# qfp100.net
KiCad netlist of a schematic drawn in EAGLE
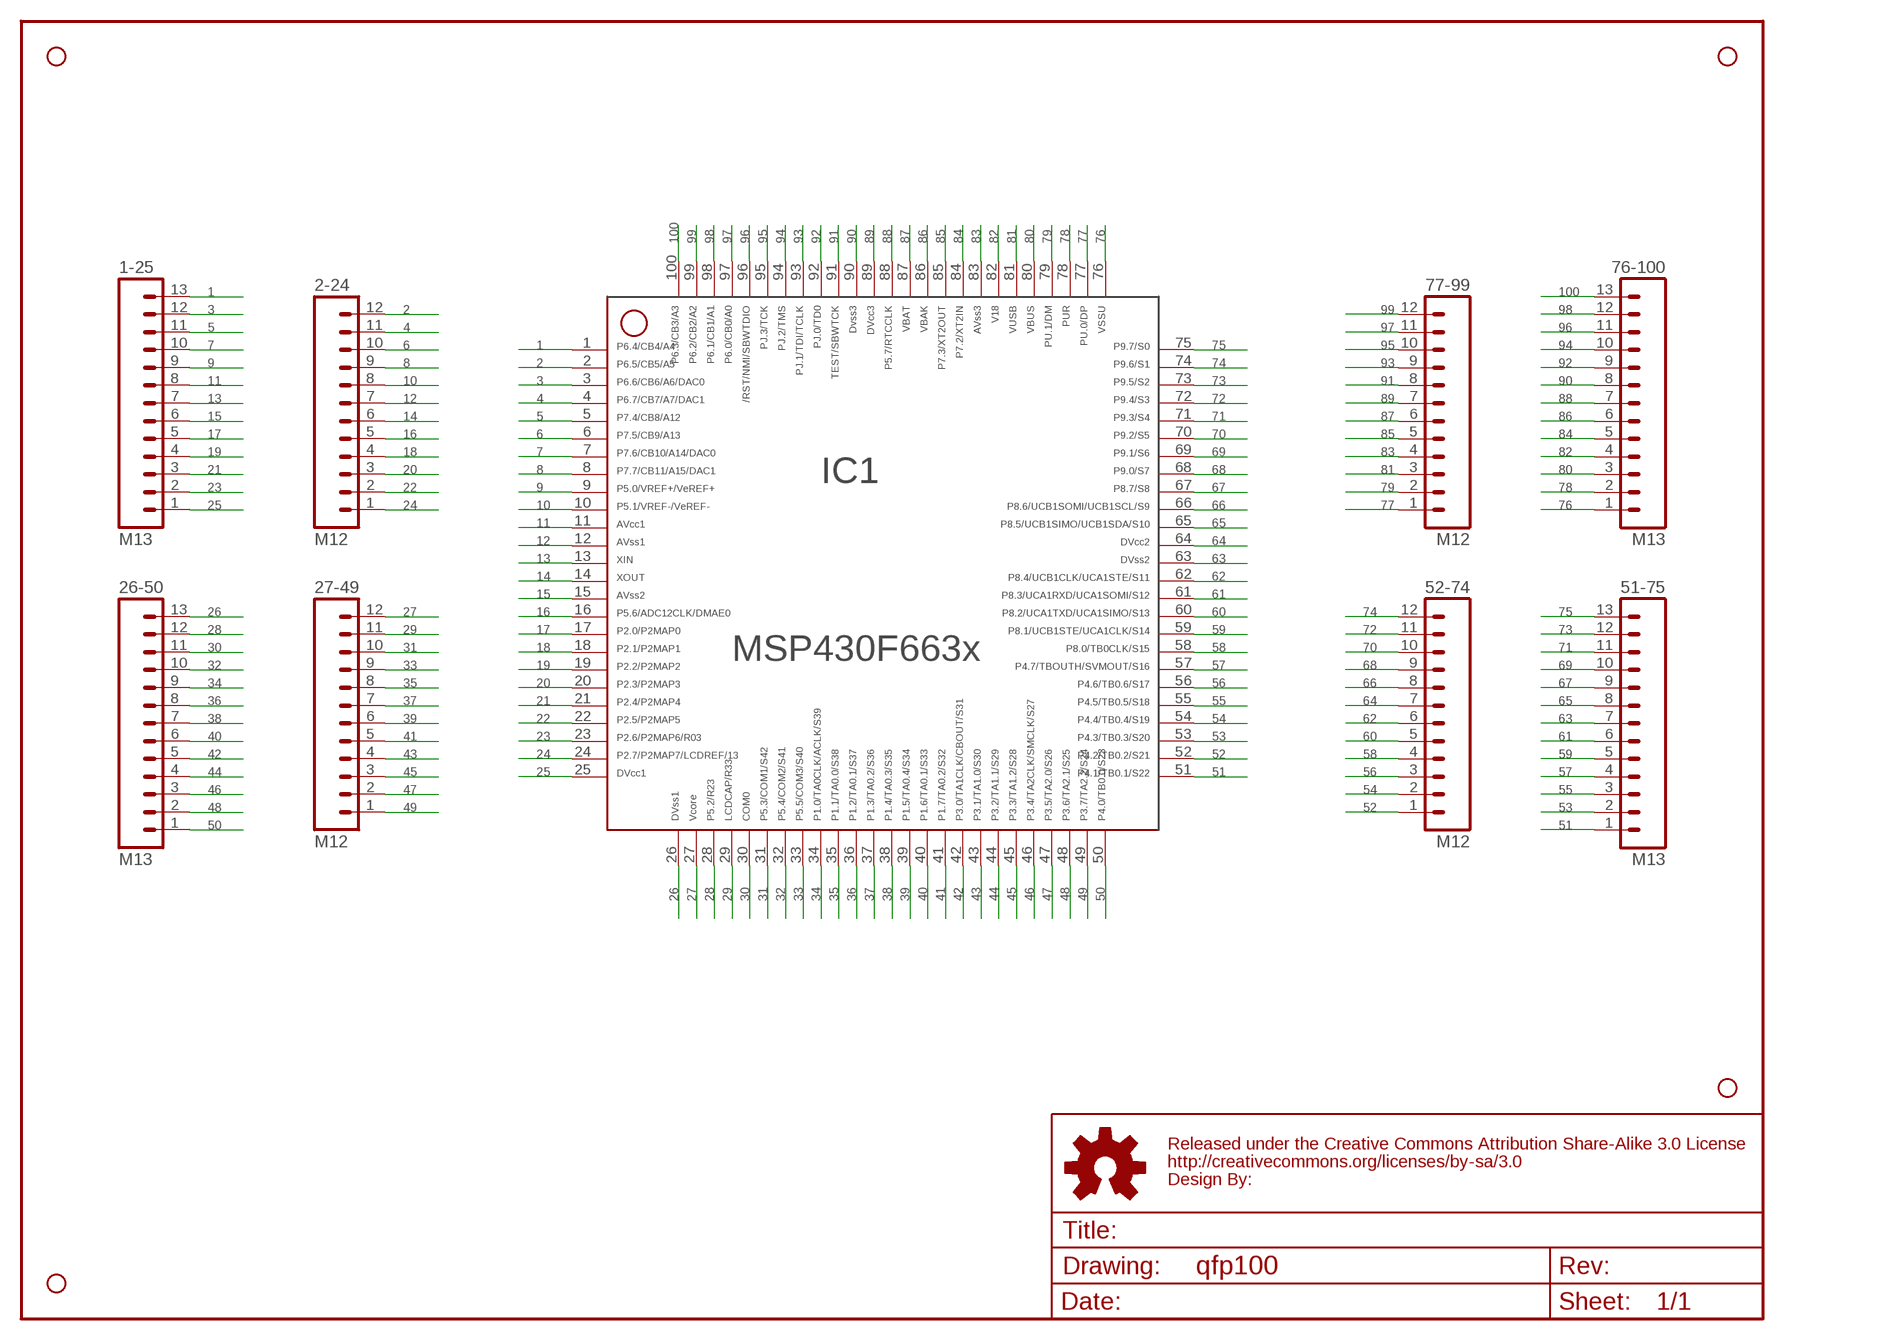
[diagram p0: schematic, sheet 1]

(export (version "E")
  (design (tool "Eeschema 10.0.6"))
  (components
    (comp (ref "1-25")
      (value "M13")
      (footprint "eagle-import:1X13")
      (libsource (lib "eagle-import") (part "M13"))
    )
    (comp (ref "2-24")
      (value "M12")
      (footprint "eagle-import:1X12")
      (libsource (lib "eagle-import") (part "M12PTH"))
    )
    (comp (ref "26-50")
      (value "M13")
      (footprint "eagle-import:1X13")
      (libsource (lib "eagle-import") (part "M13"))
    )
    (comp (ref "27-49")
      (value "M12")
      (footprint "eagle-import:1X12")
      (libsource (lib "eagle-import") (part "M12PTH"))
    )
    (comp (ref "51-75")
      (value "M13")
      (footprint "eagle-import:1X13")
      (libsource (lib "eagle-import") (part "M13"))
    )
    (comp (ref "52-74")
      (value "M12")
      (footprint "eagle-import:1X12")
      (libsource (lib "eagle-import") (part "M12PTH"))
    )
    (comp (ref "76-100")
      (value "M13")
      (footprint "eagle-import:1X13")
      (libsource (lib "eagle-import") (part "M13"))
    )
    (comp (ref "77-99")
      (value "M12")
      (footprint "eagle-import:1X12")
      (libsource (lib "eagle-import") (part "M12PTH"))
    )
    (comp (ref "FRAME1")
      (value "FRAME-LETTER")
      (footprint "eagle-import:CREATIVE_COMMONS")
      (fields
        (field (name "DESIGNER") "Jacob McDonald")
        (field (name "REV") "1")
        (field (name "TITLE") "LQFP 16-100 Pin Breakout")
      )
      (libsource (lib "eagle-import") (part "FRAME-LETTER"))
    )
    (comp (ref "IC1")
      (value "F66XX---PZ100EXTENDED")
      (footprint "eagle-import:PZ100-EXTENDED")
      (libsource (lib "eagle-import") (part "F66XX---PZ100EXTENDED"))
    )
    (comp (ref "JP1")
      (value "STAND-OFF")
      (footprint "eagle-import:STAND-OFF")
      (libsource (lib "eagle-import") (part "STAND-OFF"))
    )
    (comp (ref "JP2")
      (value "STAND-OFF")
      (footprint "eagle-import:STAND-OFF")
      (libsource (lib "eagle-import") (part "STAND-OFF"))
    )
    (comp (ref "JP3")
      (value "STAND-OFF")
      (footprint "eagle-import:STAND-OFF")
      (libsource (lib "eagle-import") (part "STAND-OFF"))
    )
    (comp (ref "JP4")
      (value "STAND-OFF")
      (footprint "eagle-import:STAND-OFF")
      (libsource (lib "eagle-import") (part "STAND-OFF"))
    )
  )
  (nets
    (net (code "1") (name "/1") (class "Default")
      (node (ref "1-25") (pin "13") (pinfunction "13_13") (pintype "passive"))
      (node (ref "IC1") (pin "1") (pinfunction "1_1") (pintype "bidirectional"))
    )
    (net (code "2") (name "/2") (class "Default")
      (node (ref "2-24") (pin "12") (pinfunction "12_12") (pintype "passive"))
      (node (ref "IC1") (pin "2") (pinfunction "2_2") (pintype "bidirectional"))
    )
    (net (code "3") (name "/3") (class "Default")
      (node (ref "1-25") (pin "12") (pinfunction "12_12") (pintype "passive"))
      (node (ref "IC1") (pin "3") (pinfunction "3_3") (pintype "bidirectional"))
    )
    (net (code "4") (name "/4") (class "Default")
      (node (ref "2-24") (pin "11") (pinfunction "11_11") (pintype "passive"))
      (node (ref "IC1") (pin "4") (pinfunction "4_4") (pintype "bidirectional"))
    )
    (net (code "5") (name "/5") (class "Default")
      (node (ref "1-25") (pin "11") (pinfunction "11_11") (pintype "passive"))
      (node (ref "IC1") (pin "5") (pinfunction "5_5") (pintype "bidirectional"))
    )
    (net (code "6") (name "/6") (class "Default")
      (node (ref "2-24") (pin "10") (pinfunction "10_10") (pintype "passive"))
      (node (ref "IC1") (pin "6") (pinfunction "6_6") (pintype "bidirectional"))
    )
    (net (code "7") (name "/7") (class "Default")
      (node (ref "1-25") (pin "10") (pinfunction "10_10") (pintype "passive"))
      (node (ref "IC1") (pin "7") (pinfunction "7_7") (pintype "bidirectional"))
    )
    (net (code "8") (name "/8") (class "Default")
      (node (ref "2-24") (pin "9") (pinfunction "9_9") (pintype "passive"))
      (node (ref "IC1") (pin "8") (pinfunction "8_8") (pintype "bidirectional"))
    )
    (net (code "9") (name "/9") (class "Default")
      (node (ref "1-25") (pin "9") (pinfunction "9_9") (pintype "passive"))
      (node (ref "IC1") (pin "9") (pinfunction "9_9") (pintype "bidirectional"))
    )
    (net (code "10") (name "/10") (class "Default")
      (node (ref "2-24") (pin "8") (pinfunction "8_8") (pintype "passive"))
      (node (ref "IC1") (pin "10") (pinfunction "10_10") (pintype "bidirectional"))
    )
    (net (code "11") (name "/11") (class "Default")
      (node (ref "1-25") (pin "8") (pinfunction "8_8") (pintype "passive"))
      (node (ref "IC1") (pin "11") (pinfunction "11_11") (pintype "power_in"))
    )
    (net (code "12") (name "/12") (class "Default")
      (node (ref "2-24") (pin "7") (pinfunction "7_7") (pintype "passive"))
      (node (ref "IC1") (pin "12") (pinfunction "12_12") (pintype "power_in"))
    )
    (net (code "13") (name "/13") (class "Default")
      (node (ref "1-25") (pin "7") (pinfunction "7_7") (pintype "passive"))
      (node (ref "IC1") (pin "13") (pinfunction "13_13") (pintype "input"))
    )
    (net (code "14") (name "/14") (class "Default")
      (node (ref "2-24") (pin "6") (pinfunction "6_6") (pintype "passive"))
      (node (ref "IC1") (pin "14") (pinfunction "14_14") (pintype "output"))
    )
    (net (code "15") (name "/15") (class "Default")
      (node (ref "1-25") (pin "6") (pinfunction "6_6") (pintype "passive"))
      (node (ref "IC1") (pin "15") (pinfunction "15_15") (pintype "power_in"))
    )
    (net (code "16") (name "/16") (class "Default")
      (node (ref "2-24") (pin "5") (pinfunction "5_5") (pintype "passive"))
      (node (ref "IC1") (pin "16") (pinfunction "16_16") (pintype "bidirectional"))
    )
    (net (code "17") (name "/17") (class "Default")
      (node (ref "1-25") (pin "5") (pinfunction "5_5") (pintype "passive"))
      (node (ref "IC1") (pin "17") (pinfunction "17_17") (pintype "bidirectional"))
    )
    (net (code "18") (name "/18") (class "Default")
      (node (ref "2-24") (pin "4") (pinfunction "4_4") (pintype "passive"))
      (node (ref "IC1") (pin "18") (pinfunction "18_18") (pintype "bidirectional"))
    )
    (net (code "19") (name "/19") (class "Default")
      (node (ref "1-25") (pin "4") (pinfunction "4_4") (pintype "passive"))
      (node (ref "IC1") (pin "19") (pinfunction "19_19") (pintype "bidirectional"))
    )
    (net (code "20") (name "/20") (class "Default")
      (node (ref "2-24") (pin "3") (pinfunction "3_3") (pintype "passive"))
      (node (ref "IC1") (pin "20") (pinfunction "20_20") (pintype "bidirectional"))
    )
    (net (code "21") (name "/21") (class "Default")
      (node (ref "1-25") (pin "3") (pinfunction "3_3") (pintype "passive"))
      (node (ref "IC1") (pin "21") (pinfunction "21_21") (pintype "bidirectional"))
    )
    (net (code "22") (name "/22") (class "Default")
      (node (ref "2-24") (pin "2") (pinfunction "2_2") (pintype "passive"))
      (node (ref "IC1") (pin "22") (pinfunction "22_22") (pintype "bidirectional"))
    )
    (net (code "23") (name "/23") (class "Default")
      (node (ref "1-25") (pin "2") (pinfunction "2_2") (pintype "passive"))
      (node (ref "IC1") (pin "23") (pinfunction "23_23") (pintype "bidirectional"))
    )
    (net (code "24") (name "/24") (class "Default")
      (node (ref "2-24") (pin "1") (pinfunction "1_1") (pintype "passive"))
      (node (ref "IC1") (pin "24") (pinfunction "24_24") (pintype "bidirectional"))
    )
    (net (code "25") (name "/25") (class "Default")
      (node (ref "1-25") (pin "1") (pinfunction "1_1") (pintype "passive"))
      (node (ref "IC1") (pin "25") (pinfunction "25_25") (pintype "power_in"))
    )
    (net (code "26") (name "/26") (class "Default")
      (node (ref "26-50") (pin "13") (pinfunction "13_13") (pintype "passive"))
      (node (ref "IC1") (pin "26") (pinfunction "26_26") (pintype "power_in"))
    )
    (net (code "27") (name "/27") (class "Default")
      (node (ref "27-49") (pin "12") (pinfunction "12_12") (pintype "passive"))
      (node (ref "IC1") (pin "27") (pinfunction "27_27") (pintype "bidirectional"))
    )
    (net (code "28") (name "/28") (class "Default")
      (node (ref "26-50") (pin "12") (pinfunction "12_12") (pintype "passive"))
      (node (ref "IC1") (pin "28") (pinfunction "28_28") (pintype "bidirectional"))
    )
    (net (code "29") (name "/29") (class "Default")
      (node (ref "27-49") (pin "11") (pinfunction "11_11") (pintype "passive"))
      (node (ref "IC1") (pin "29") (pinfunction "29_29") (pintype "bidirectional"))
    )
    (net (code "30") (name "/30") (class "Default")
      (node (ref "26-50") (pin "11") (pinfunction "11_11") (pintype "passive"))
      (node (ref "IC1") (pin "30") (pinfunction "30_30") (pintype "bidirectional"))
    )
    (net (code "31") (name "/31") (class "Default")
      (node (ref "27-49") (pin "10") (pinfunction "10_10") (pintype "passive"))
      (node (ref "IC1") (pin "31") (pinfunction "31_31") (pintype "bidirectional"))
    )
    (net (code "32") (name "/32") (class "Default")
      (node (ref "26-50") (pin "10") (pinfunction "10_10") (pintype "passive"))
      (node (ref "IC1") (pin "32") (pinfunction "32_32") (pintype "bidirectional"))
    )
    (net (code "33") (name "/33") (class "Default")
      (node (ref "27-49") (pin "9") (pinfunction "9_9") (pintype "passive"))
      (node (ref "IC1") (pin "33") (pinfunction "33_33") (pintype "bidirectional"))
    )
    (net (code "34") (name "/34") (class "Default")
      (node (ref "26-50") (pin "9") (pinfunction "9_9") (pintype "passive"))
      (node (ref "IC1") (pin "34") (pinfunction "34_34") (pintype "bidirectional"))
    )
    (net (code "35") (name "/35") (class "Default")
      (node (ref "27-49") (pin "8") (pinfunction "8_8") (pintype "passive"))
      (node (ref "IC1") (pin "35") (pinfunction "35_35") (pintype "bidirectional"))
    )
    (net (code "36") (name "/36") (class "Default")
      (node (ref "26-50") (pin "8") (pinfunction "8_8") (pintype "passive"))
      (node (ref "IC1") (pin "36") (pinfunction "36_36") (pintype "bidirectional"))
    )
    (net (code "37") (name "/37") (class "Default")
      (node (ref "27-49") (pin "7") (pinfunction "7_7") (pintype "passive"))
      (node (ref "IC1") (pin "37") (pinfunction "37_37") (pintype "bidirectional"))
    )
    (net (code "38") (name "/38") (class "Default")
      (node (ref "26-50") (pin "7") (pinfunction "7_7") (pintype "passive"))
      (node (ref "IC1") (pin "38") (pinfunction "38_38") (pintype "bidirectional"))
    )
    (net (code "39") (name "/39") (class "Default")
      (node (ref "27-49") (pin "6") (pinfunction "6_6") (pintype "passive"))
      (node (ref "IC1") (pin "39") (pinfunction "39_39") (pintype "bidirectional"))
    )
    (net (code "40") (name "/40") (class "Default")
      (node (ref "26-50") (pin "6") (pinfunction "6_6") (pintype "passive"))
      (node (ref "IC1") (pin "40") (pinfunction "40_40") (pintype "bidirectional"))
    )
    (net (code "41") (name "/41") (class "Default")
      (node (ref "27-49") (pin "5") (pinfunction "5_5") (pintype "passive"))
      (node (ref "IC1") (pin "41") (pinfunction "41_41") (pintype "bidirectional"))
    )
    (net (code "42") (name "/42") (class "Default")
      (node (ref "26-50") (pin "5") (pinfunction "5_5") (pintype "passive"))
      (node (ref "IC1") (pin "42") (pinfunction "42_42") (pintype "bidirectional"))
    )
    (net (code "43") (name "/43") (class "Default")
      (node (ref "27-49") (pin "4") (pinfunction "4_4") (pintype "passive"))
      (node (ref "IC1") (pin "43") (pinfunction "43_43") (pintype "bidirectional"))
    )
    (net (code "44") (name "/44") (class "Default")
      (node (ref "26-50") (pin "4") (pinfunction "4_4") (pintype "passive"))
      (node (ref "IC1") (pin "44") (pinfunction "44_44") (pintype "bidirectional"))
    )
    (net (code "45") (name "/45") (class "Default")
      (node (ref "27-49") (pin "3") (pinfunction "3_3") (pintype "passive"))
      (node (ref "IC1") (pin "45") (pinfunction "45_45") (pintype "bidirectional"))
    )
    (net (code "46") (name "/46") (class "Default")
      (node (ref "26-50") (pin "3") (pinfunction "3_3") (pintype "passive"))
      (node (ref "IC1") (pin "46") (pinfunction "46_46") (pintype "bidirectional"))
    )
    (net (code "47") (name "/47") (class "Default")
      (node (ref "27-49") (pin "2") (pinfunction "2_2") (pintype "passive"))
      (node (ref "IC1") (pin "47") (pinfunction "47_47") (pintype "bidirectional"))
    )
    (net (code "48") (name "/48") (class "Default")
      (node (ref "26-50") (pin "2") (pinfunction "2_2") (pintype "passive"))
      (node (ref "IC1") (pin "48") (pinfunction "48_48") (pintype "bidirectional"))
    )
    (net (code "49") (name "/49") (class "Default")
      (node (ref "27-49") (pin "1") (pinfunction "1_1") (pintype "passive"))
      (node (ref "IC1") (pin "49") (pinfunction "49_49") (pintype "bidirectional"))
    )
    (net (code "50") (name "/50") (class "Default")
      (node (ref "26-50") (pin "1") (pinfunction "1_1") (pintype "passive"))
      (node (ref "IC1") (pin "50") (pinfunction "50_50") (pintype "bidirectional"))
    )
    (net (code "51") (name "/51") (class "Default")
      (node (ref "51-75") (pin "1") (pinfunction "1_1") (pintype "passive"))
      (node (ref "IC1") (pin "51") (pinfunction "51_51") (pintype "bidirectional"))
    )
    (net (code "52") (name "/52") (class "Default")
      (node (ref "52-74") (pin "1") (pinfunction "1_1") (pintype "passive"))
      (node (ref "IC1") (pin "52") (pinfunction "52_52") (pintype "bidirectional"))
    )
    (net (code "53") (name "/53") (class "Default")
      (node (ref "51-75") (pin "2") (pinfunction "2_2") (pintype "passive"))
      (node (ref "IC1") (pin "53") (pinfunction "53_53") (pintype "bidirectional"))
    )
    (net (code "54") (name "/54") (class "Default")
      (node (ref "52-74") (pin "2") (pinfunction "2_2") (pintype "passive"))
      (node (ref "IC1") (pin "54") (pinfunction "54_54") (pintype "bidirectional"))
    )
    (net (code "55") (name "/55") (class "Default")
      (node (ref "51-75") (pin "3") (pinfunction "3_3") (pintype "passive"))
      (node (ref "IC1") (pin "55") (pinfunction "55_55") (pintype "bidirectional"))
    )
    (net (code "56") (name "/56") (class "Default")
      (node (ref "52-74") (pin "3") (pinfunction "3_3") (pintype "passive"))
      (node (ref "IC1") (pin "56") (pinfunction "56_56") (pintype "bidirectional"))
    )
    (net (code "57") (name "/57") (class "Default")
      (node (ref "51-75") (pin "4") (pinfunction "4_4") (pintype "passive"))
      (node (ref "IC1") (pin "57") (pinfunction "57_57") (pintype "bidirectional"))
    )
    (net (code "58") (name "/58") (class "Default")
      (node (ref "52-74") (pin "4") (pinfunction "4_4") (pintype "passive"))
      (node (ref "IC1") (pin "58") (pinfunction "58_58") (pintype "bidirectional"))
    )
    (net (code "59") (name "/59") (class "Default")
      (node (ref "51-75") (pin "5") (pinfunction "5_5") (pintype "passive"))
      (node (ref "IC1") (pin "59") (pinfunction "59_59") (pintype "bidirectional"))
    )
    (net (code "60") (name "/60") (class "Default")
      (node (ref "52-74") (pin "5") (pinfunction "5_5") (pintype "passive"))
      (node (ref "IC1") (pin "60") (pinfunction "60_60") (pintype "bidirectional"))
    )
    (net (code "61") (name "/61") (class "Default")
      (node (ref "51-75") (pin "6") (pinfunction "6_6") (pintype "passive"))
      (node (ref "IC1") (pin "61") (pinfunction "61_61") (pintype "bidirectional"))
    )
    (net (code "62") (name "/62") (class "Default")
      (node (ref "52-74") (pin "6") (pinfunction "6_6") (pintype "passive"))
      (node (ref "IC1") (pin "62") (pinfunction "62_62") (pintype "bidirectional"))
    )
    (net (code "63") (name "/63") (class "Default")
      (node (ref "51-75") (pin "7") (pinfunction "7_7") (pintype "passive"))
      (node (ref "IC1") (pin "63") (pinfunction "63_63") (pintype "power_in"))
    )
    (net (code "64") (name "/64") (class "Default")
      (node (ref "52-74") (pin "7") (pinfunction "7_7") (pintype "passive"))
      (node (ref "IC1") (pin "64") (pinfunction "64_64") (pintype "power_in"))
    )
    (net (code "65") (name "/65") (class "Default")
      (node (ref "51-75") (pin "8") (pinfunction "8_8") (pintype "passive"))
      (node (ref "IC1") (pin "65") (pinfunction "65_65") (pintype "bidirectional"))
    )
    (net (code "66") (name "/66") (class "Default")
      (node (ref "52-74") (pin "8") (pinfunction "8_8") (pintype "passive"))
      (node (ref "IC1") (pin "66") (pinfunction "66_66") (pintype "bidirectional"))
    )
    (net (code "67") (name "/67") (class "Default")
      (node (ref "51-75") (pin "9") (pinfunction "9_9") (pintype "passive"))
      (node (ref "IC1") (pin "67") (pinfunction "67_67") (pintype "bidirectional"))
    )
    (net (code "68") (name "/68") (class "Default")
      (node (ref "52-74") (pin "9") (pinfunction "9_9") (pintype "passive"))
      (node (ref "IC1") (pin "68") (pinfunction "68_68") (pintype "bidirectional"))
    )
    (net (code "69") (name "/69") (class "Default")
      (node (ref "51-75") (pin "10") (pinfunction "10_10") (pintype "passive"))
      (node (ref "IC1") (pin "69") (pinfunction "69_69") (pintype "bidirectional"))
    )
    (net (code "70") (name "/70") (class "Default")
      (node (ref "52-74") (pin "10") (pinfunction "10_10") (pintype "passive"))
      (node (ref "IC1") (pin "70") (pinfunction "70_70") (pintype "bidirectional"))
    )
    (net (code "71") (name "/71") (class "Default")
      (node (ref "51-75") (pin "11") (pinfunction "11_11") (pintype "passive"))
      (node (ref "IC1") (pin "71") (pinfunction "71_71") (pintype "bidirectional"))
    )
    (net (code "72") (name "/72") (class "Default")
      (node (ref "52-74") (pin "11") (pinfunction "11_11") (pintype "passive"))
      (node (ref "IC1") (pin "72") (pinfunction "72_72") (pintype "bidirectional"))
    )
    (net (code "73") (name "/73") (class "Default")
      (node (ref "51-75") (pin "12") (pinfunction "12_12") (pintype "passive"))
      (node (ref "IC1") (pin "73") (pinfunction "73_73") (pintype "bidirectional"))
    )
    (net (code "74") (name "/74") (class "Default")
      (node (ref "52-74") (pin "12") (pinfunction "12_12") (pintype "passive"))
      (node (ref "IC1") (pin "74") (pinfunction "74_74") (pintype "bidirectional"))
    )
    (net (code "75") (name "/75") (class "Default")
      (node (ref "51-75") (pin "13") (pinfunction "13_13") (pintype "passive"))
      (node (ref "IC1") (pin "75") (pinfunction "75_75") (pintype "bidirectional"))
    )
    (net (code "76") (name "/76") (class "Default")
      (node (ref "76-100") (pin "1") (pinfunction "1_1") (pintype "passive"))
      (node (ref "IC1") (pin "76") (pinfunction "76_76") (pintype "bidirectional"))
    )
    (net (code "77") (name "/77") (class "Default")
      (node (ref "77-99") (pin "1") (pinfunction "1_1") (pintype "passive"))
      (node (ref "IC1") (pin "77") (pinfunction "77_77") (pintype "bidirectional"))
    )
    (net (code "78") (name "/78") (class "Default")
      (node (ref "76-100") (pin "2") (pinfunction "2_2") (pintype "passive"))
      (node (ref "IC1") (pin "78") (pinfunction "78_78") (pintype "bidirectional"))
    )
    (net (code "79") (name "/79") (class "Default")
      (node (ref "77-99") (pin "2") (pinfunction "2_2") (pintype "passive"))
      (node (ref "IC1") (pin "79") (pinfunction "79_79") (pintype "bidirectional"))
    )
    (net (code "80") (name "/80") (class "Default")
      (node (ref "76-100") (pin "3") (pinfunction "3_3") (pintype "passive"))
      (node (ref "IC1") (pin "80") (pinfunction "80_80") (pintype "bidirectional"))
    )
    (net (code "81") (name "/81") (class "Default")
      (node (ref "77-99") (pin "3") (pinfunction "3_3") (pintype "passive"))
      (node (ref "IC1") (pin "81") (pinfunction "81_81") (pintype "bidirectional"))
    )
    (net (code "82") (name "/82") (class "Default")
      (node (ref "76-100") (pin "4") (pinfunction "4_4") (pintype "passive"))
      (node (ref "IC1") (pin "82") (pinfunction "82_82") (pintype "bidirectional"))
    )
    (net (code "83") (name "/83") (class "Default")
      (node (ref "77-99") (pin "4") (pinfunction "4_4") (pintype "passive"))
      (node (ref "IC1") (pin "83") (pinfunction "83_83") (pintype "power_in"))
    )
    (net (code "84") (name "/84") (class "Default")
      (node (ref "76-100") (pin "5") (pinfunction "5_5") (pintype "passive"))
      (node (ref "IC1") (pin "84") (pinfunction "84_84") (pintype "bidirectional"))
    )
    (net (code "85") (name "/85") (class "Default")
      (node (ref "77-99") (pin "5") (pinfunction "5_5") (pintype "passive"))
      (node (ref "IC1") (pin "85") (pinfunction "85_85") (pintype "bidirectional"))
    )
    (net (code "86") (name "/86") (class "Default")
      (node (ref "76-100") (pin "6") (pinfunction "6_6") (pintype "passive"))
      (node (ref "IC1") (pin "86") (pinfunction "86_86") (pintype "bidirectional"))
    )
    (net (code "87") (name "/87") (class "Default")
      (node (ref "77-99") (pin "6") (pinfunction "6_6") (pintype "passive"))
      (node (ref "IC1") (pin "87") (pinfunction "87_87") (pintype "bidirectional"))
    )
    (net (code "88") (name "/88") (class "Default")
      (node (ref "76-100") (pin "7") (pinfunction "7_7") (pintype "passive"))
      (node (ref "IC1") (pin "88") (pinfunction "88_88") (pintype "bidirectional"))
    )
    (net (code "89") (name "/89") (class "Default")
      (node (ref "77-99") (pin "7") (pinfunction "7_7") (pintype "passive"))
      (node (ref "IC1") (pin "89") (pinfunction "89_89") (pintype "power_in"))
    )
    (net (code "90") (name "/90") (class "Default")
      (node (ref "76-100") (pin "8") (pinfunction "8_8") (pintype "passive"))
      (node (ref "IC1") (pin "90") (pinfunction "90_90") (pintype "power_in"))
    )
    (net (code "91") (name "/91") (class "Default")
      (node (ref "77-99") (pin "8") (pinfunction "8_8") (pintype "passive"))
      (node (ref "IC1") (pin "91") (pinfunction "91_91") (pintype "input"))
    )
    (net (code "92") (name "/92") (class "Default")
      (node (ref "76-100") (pin "9") (pinfunction "9_9") (pintype "passive"))
      (node (ref "IC1") (pin "92") (pinfunction "92_92") (pintype "bidirectional"))
    )
    (net (code "93") (name "/93") (class "Default")
      (node (ref "77-99") (pin "9") (pinfunction "9_9") (pintype "passive"))
      (node (ref "IC1") (pin "93") (pinfunction "93_93") (pintype "bidirectional"))
    )
    (net (code "94") (name "/94") (class "Default")
      (node (ref "76-100") (pin "10") (pinfunction "10_10") (pintype "passive"))
      (node (ref "IC1") (pin "94") (pinfunction "94_94") (pintype "bidirectional"))
    )
    (net (code "95") (name "/95") (class "Default")
      (node (ref "77-99") (pin "10") (pinfunction "10_10") (pintype "passive"))
      (node (ref "IC1") (pin "95") (pinfunction "95_95") (pintype "bidirectional"))
    )
    (net (code "96") (name "/96") (class "Default")
      (node (ref "76-100") (pin "11") (pinfunction "11_11") (pintype "passive"))
      (node (ref "IC1") (pin "96") (pinfunction "96_96") (pintype "bidirectional"))
    )
    (net (code "97") (name "/97") (class "Default")
      (node (ref "77-99") (pin "11") (pinfunction "11_11") (pintype "passive"))
      (node (ref "IC1") (pin "97") (pinfunction "97_97") (pintype "bidirectional"))
    )
    (net (code "98") (name "/98") (class "Default")
      (node (ref "76-100") (pin "12") (pinfunction "12_12") (pintype "passive"))
      (node (ref "IC1") (pin "98") (pinfunction "98_98") (pintype "bidirectional"))
    )
    (net (code "99") (name "/99") (class "Default")
      (node (ref "77-99") (pin "12") (pinfunction "12_12") (pintype "passive"))
      (node (ref "IC1") (pin "99") (pinfunction "99_99") (pintype "bidirectional"))
    )
    (net (code "100") (name "/100") (class "Default")
      (node (ref "76-100") (pin "13") (pinfunction "13_13") (pintype "passive"))
      (node (ref "IC1") (pin "100") (pinfunction "100_100") (pintype "bidirectional"))
    )
  )
)
